# smokoino.net
KiCad netlist of a schematic drawn in EAGLE
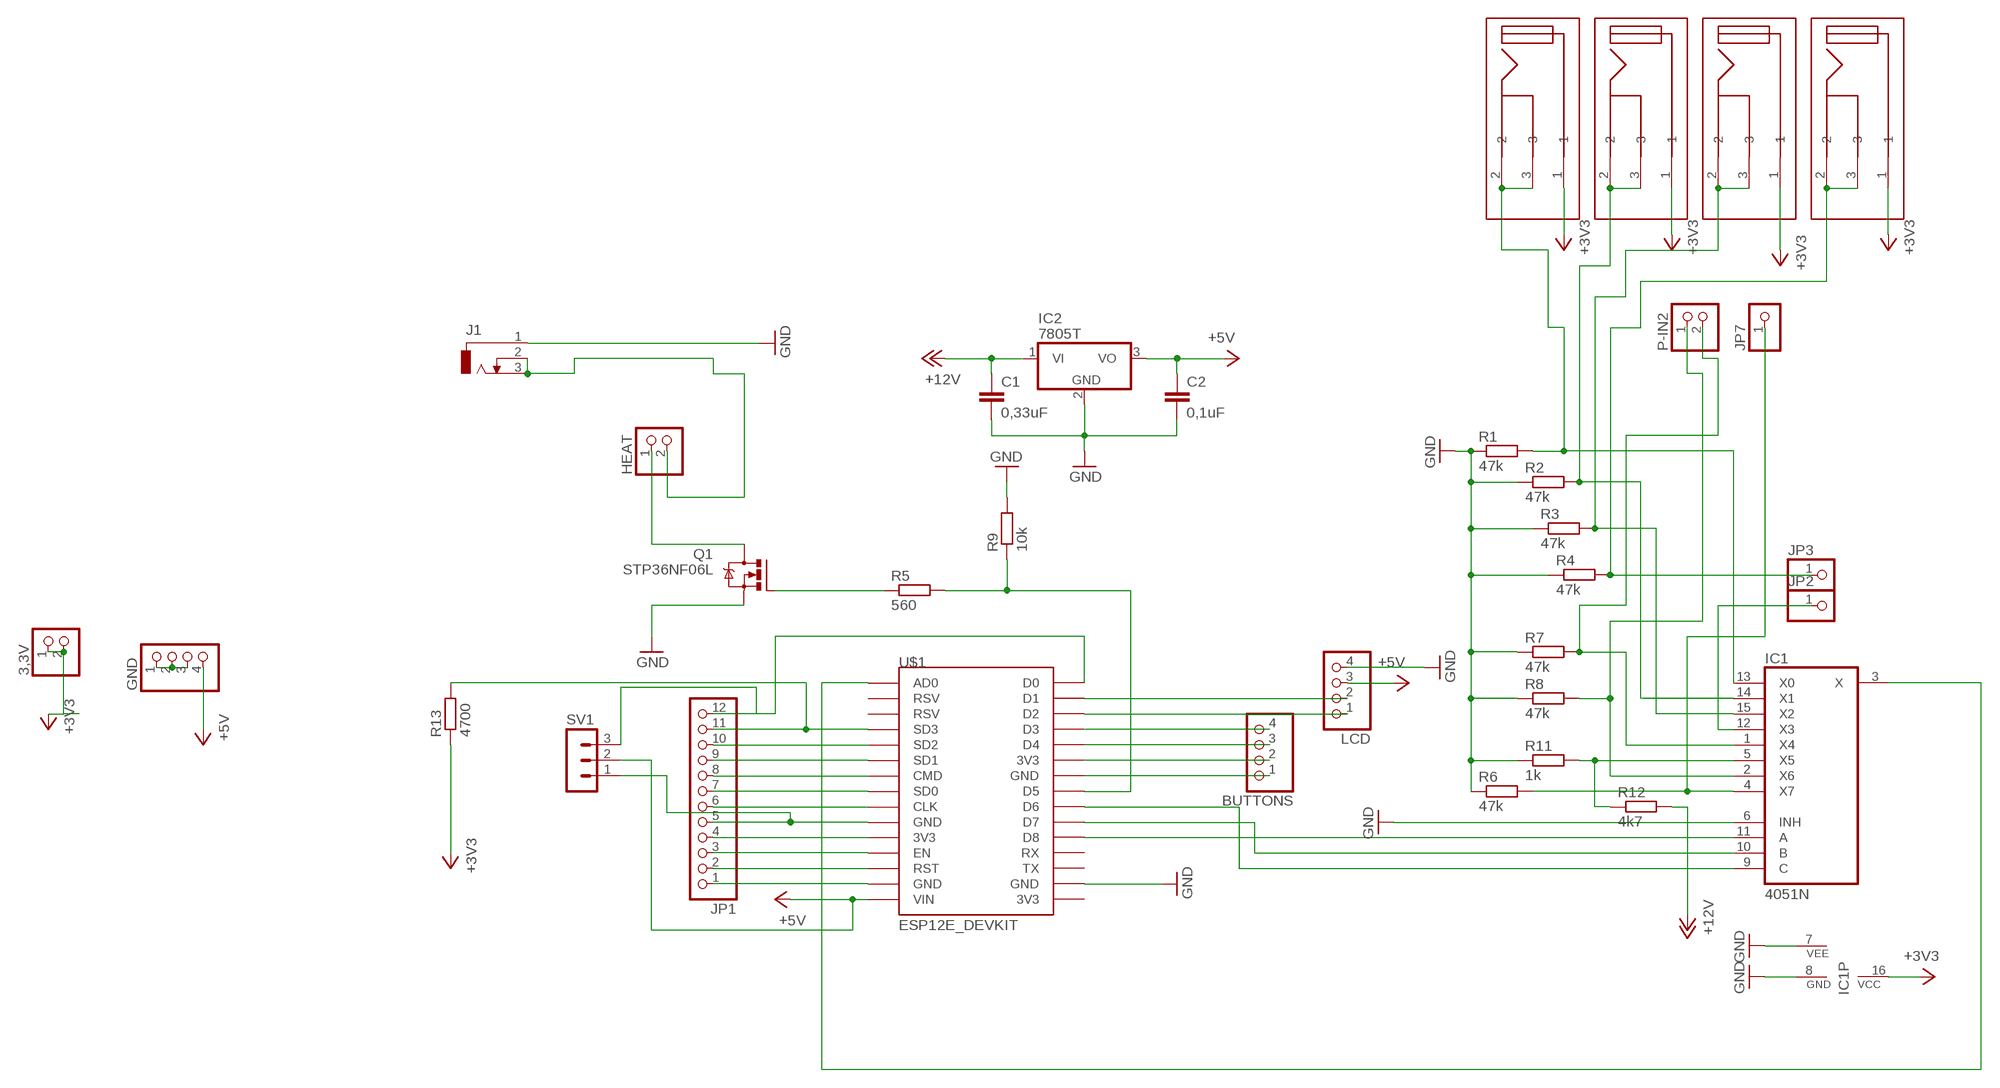
[diagram p0: schematic, sheet 1]

(export (version "E")
  (design (tool "Eeschema 10.0.6"))
  (components
    (comp (ref "3,3V")
      (value "PINHD-1X2")
      (footprint "eagle-import:1X02")
      (libsource (lib "eagle-import") (part "PINHD-1X2"))
    )
    (comp (ref "BUTTONS")
      (value "PINHD-1X4")
      (footprint "eagle-import:1X04")
      (libsource (lib "eagle-import") (part "PINHD-1X4"))
    )
    (comp (ref "C1")
      (value "0,33uF")
      (footprint "eagle-import:C5B2.5")
      (libsource (lib "eagle-import") (part "C5/2.5"))
    )
    (comp (ref "C2")
      (value "0,1uF")
      (footprint "eagle-import:C5B2.5")
      (libsource (lib "eagle-import") (part "C5/2.5"))
    )
    (comp (ref "GND")
      (value "PINHD-1X4")
      (footprint "eagle-import:1X04")
      (libsource (lib "eagle-import") (part "PINHD-1X4"))
    )
    (comp (ref "HEAT")
      (value "PINHD-1X2")
      (footprint "eagle-import:1X02")
      (libsource (lib "eagle-import") (part "PINHD-1X2"))
    )
    (comp (ref "IC1")
      (value "4051N")
      (footprint "eagle-import:DIL16")
      (libsource (lib "eagle-import") (part "4051N"))
    )
    (comp (ref "IC2")
      (value "7805T")
      (footprint "eagle-import:TO220H")
      (libsource (lib "eagle-import") (part "78T05"))
    )
    (comp (ref "J1")
      (value "DCJ0303")
      (footprint "eagle-import:DCJ0303")
      (libsource (lib "eagle-import") (part "DCJ0303"))
    )
    (comp (ref "JP1")
      (value "PINHD-1X12")
      (footprint "eagle-import:1X12")
      (libsource (lib "eagle-import") (part "PINHD-1X12"))
    )
    (comp (ref "JP2")
      (value "PINHD-1X1")
      (footprint "eagle-import:1X01")
      (libsource (lib "eagle-import") (part "PINHD-1X1"))
    )
    (comp (ref "JP3")
      (value "PINHD-1X1")
      (footprint "eagle-import:1X01")
      (libsource (lib "eagle-import") (part "PINHD-1X1"))
    )
    (comp (ref "JP7")
      (value "PINHD-1X1")
      (footprint "eagle-import:1X01")
      (libsource (lib "eagle-import") (part "PINHD-1X1"))
    )
    (comp (ref "LCD")
      (value "PINHD-1X4")
      (footprint "eagle-import:1X04")
      (libsource (lib "eagle-import") (part "PINHD-1X4"))
    )
    (comp (ref "P-IN2")
      (value "PINHD-1X2")
      (footprint "eagle-import:1X02")
      (libsource (lib "eagle-import") (part "PINHD-1X2"))
    )
    (comp (ref "Q1")
      (value "STP36NF06L")
      (footprint "eagle-import:TO220BV")
      (libsource (lib "eagle-import") (part "IRF540"))
    )
    (comp (ref "R1")
      (value "47k")
      (footprint "eagle-import:0207_10")
      (libsource (lib "eagle-import") (part "R-EU_0207/10"))
    )
    (comp (ref "R2")
      (value "47k")
      (footprint "eagle-import:0207_10")
      (libsource (lib "eagle-import") (part "R-EU_0207/10"))
    )
    (comp (ref "R3")
      (value "47k")
      (footprint "eagle-import:0207_10")
      (libsource (lib "eagle-import") (part "R-EU_0207/10"))
    )
    (comp (ref "R4")
      (value "47k")
      (footprint "eagle-import:0207_10")
      (libsource (lib "eagle-import") (part "R-EU_0207/10"))
    )
    (comp (ref "R5")
      (value "560")
      (footprint "eagle-import:0207_10")
      (libsource (lib "eagle-import") (part "R-EU_0207/10"))
    )
    (comp (ref "R6")
      (value "47k")
      (footprint "eagle-import:0207_10")
      (libsource (lib "eagle-import") (part "R-EU_0207/10"))
    )
    (comp (ref "R7")
      (value "47k")
      (footprint "eagle-import:0207_10")
      (libsource (lib "eagle-import") (part "R-EU_0207/10"))
    )
    (comp (ref "R8")
      (value "47k")
      (footprint "eagle-import:0207_10")
      (libsource (lib "eagle-import") (part "R-EU_0207/10"))
    )
    (comp (ref "R9")
      (value "10k")
      (footprint "eagle-import:0207_10")
      (libsource (lib "eagle-import") (part "R-EU_0207/10"))
    )
    (comp (ref "R11")
      (value "1k")
      (footprint "eagle-import:0207_10")
      (libsource (lib "eagle-import") (part "R-EU_0207/10"))
    )
    (comp (ref "R12")
      (value "4k7")
      (footprint "eagle-import:0207_10")
      (libsource (lib "eagle-import") (part "R-EU_0207/10"))
    )
    (comp (ref "R13")
      (value "4700")
      (footprint "eagle-import:0207_10")
      (libsource (lib "eagle-import") (part "R-EU_0207/10"))
    )
    (comp (ref "SV1")
      (value "MA03-1")
      (footprint "eagle-import:MA03-1")
      (libsource (lib "eagle-import") (part "MA03-1"))
    )
    (comp (ref "U$1")
      (value "ESP12E_DEVKIT")
      (footprint "eagle-import:ESP12E_DEVKIT")
      (libsource (lib "eagle-import") (part "ESP12E_DEVKIT"))
    )
    (comp (ref "U$3")
      (value "JACK_2_5")
      (footprint "eagle-import:JACK_2_5")
      (libsource (lib "eagle-import") (part "JACK_2_5"))
    )
    (comp (ref "U$4")
      (value "JACK_2_5")
      (footprint "eagle-import:JACK_2_5")
      (libsource (lib "eagle-import") (part "JACK_2_5"))
    )
    (comp (ref "U$5")
      (value "JACK_2_5")
      (footprint "eagle-import:JACK_2_5")
      (libsource (lib "eagle-import") (part "JACK_2_5"))
    )
    (comp (ref "U$6")
      (value "JACK_2_5")
      (footprint "eagle-import:JACK_2_5")
      (libsource (lib "eagle-import") (part "JACK_2_5"))
    )
  )
  (nets
    (net (code "1") (name "+3V3") (class "Default")
      (node (ref "3,3V") (pin "1") (pinfunction "1_1") (pintype "passive"))
      (node (ref "3,3V") (pin "2") (pinfunction "2_2") (pintype "passive"))
      (node (ref "IC1") (pin "16") (pinfunction "VCC_16") (pintype "power_in"))
      (node (ref "JP1") (pin "4") (pinfunction "4_4") (pintype "passive"))
      (node (ref "R13") (pin "1") (pinfunction "1_1") (pintype "passive"))
      (node (ref "U$1") (pin "3V3@0") (pinfunction "3V3_3V3@0") (pintype "bidirectional"))
      (node (ref "U$3") (pin "1") (pinfunction "1_1") (pintype "bidirectional"))
      (node (ref "U$4") (pin "1") (pinfunction "1_1") (pintype "bidirectional"))
      (node (ref "U$5") (pin "1") (pinfunction "1_1") (pintype "bidirectional"))
      (node (ref "U$6") (pin "1") (pinfunction "1_1") (pintype "bidirectional"))
    )
    (net (code "2") (name "+5V") (class "Default")
      (node (ref "C2") (pin "1") (pinfunction "1_1") (pintype "passive"))
      (node (ref "GND") (pin "4") (pinfunction "4_4") (pintype "passive"))
      (node (ref "IC2") (pin "3") (pinfunction "VO_3") (pintype "passive"))
      (node (ref "LCD") (pin "3") (pinfunction "3_3") (pintype "passive"))
      (node (ref "SV1") (pin "2") (pinfunction "2_2") (pintype "passive"))
      (node (ref "U$1") (pin "VIN") (pinfunction "VIN_VIN") (pintype "bidirectional"))
    )
    (net (code "3") (name "+12V") (class "Default")
      (node (ref "C1") (pin "1") (pinfunction "1_1") (pintype "passive"))
      (node (ref "HEAT") (pin "2") (pinfunction "2_2") (pintype "passive"))
      (node (ref "IC2") (pin "1") (pinfunction "VI_1") (pintype "input"))
      (node (ref "J1") (pin "2") (pinfunction "2_2") (pintype "passive"))
      (node (ref "J1") (pin "3") (pinfunction "3_3") (pintype "passive"))
      (node (ref "R12") (pin "2") (pinfunction "2_2") (pintype "passive"))
    )
    (net (code "4") (name "GND") (class "Default")
      (node (ref "BUTTONS") (pin "1") (pinfunction "1_1") (pintype "passive"))
      (node (ref "C1") (pin "2") (pinfunction "2_2") (pintype "passive"))
      (node (ref "C2") (pin "2") (pinfunction "2_2") (pintype "passive"))
      (node (ref "GND") (pin "1") (pinfunction "1_1") (pintype "passive"))
      (node (ref "GND") (pin "2") (pinfunction "2_2") (pintype "passive"))
      (node (ref "GND") (pin "3") (pinfunction "3_3") (pintype "passive"))
      (node (ref "IC1") (pin "6") (pinfunction "INH_6") (pintype "input"))
      (node (ref "IC1") (pin "7") (pinfunction "VEE_7") (pintype "power_in"))
      (node (ref "IC1") (pin "8") (pinfunction "GND_8") (pintype "power_in"))
      (node (ref "IC2") (pin "2") (pinfunction "GND_2") (pintype "passive"))
      (node (ref "J1") (pin "1") (pinfunction "1_1") (pintype "passive"))
      (node (ref "JP1") (pin "1") (pinfunction "1_1") (pintype "passive"))
      (node (ref "JP1") (pin "5") (pinfunction "5_5") (pintype "passive"))
      (node (ref "LCD") (pin "4") (pinfunction "4_4") (pintype "passive"))
      (node (ref "Q1") (pin "S") (pinfunction "S_S") (pintype "passive"))
      (node (ref "R1") (pin "1") (pinfunction "1_1") (pintype "passive"))
      (node (ref "R11") (pin "1") (pinfunction "1_1") (pintype "passive"))
      (node (ref "R2") (pin "1") (pinfunction "1_1") (pintype "passive"))
      (node (ref "R3") (pin "1") (pinfunction "1_1") (pintype "passive"))
      (node (ref "R4") (pin "1") (pinfunction "1_1") (pintype "passive"))
      (node (ref "R6") (pin "1") (pinfunction "1_1") (pintype "passive"))
      (node (ref "R7") (pin "1") (pinfunction "1_1") (pintype "passive"))
      (node (ref "R8") (pin "1") (pinfunction "1_1") (pintype "passive"))
      (node (ref "R9") (pin "2") (pinfunction "2_2") (pintype "passive"))
      (node (ref "SV1") (pin "1") (pinfunction "1_1") (pintype "passive"))
      (node (ref "U$1") (pin "GND@0") (pinfunction "GND_GND@0") (pintype "bidirectional"))
      (node (ref "U$1") (pin "GND@1") (pinfunction "GND_GND@1") (pintype "bidirectional"))
      (node (ref "U$1") (pin "GND@2") (pinfunction "GND_GND@2") (pintype "bidirectional"))
      (node (ref "U$1") (pin "GND@3") (pinfunction "GND_GND@3") (pintype "bidirectional"))
    )
    (net (code "5") (name "Net-(BUTTONS-Pad2)") (class "Default")
      (node (ref "BUTTONS") (pin "2") (pinfunction "2_2") (pintype "passive"))
      (node (ref "U$1") (pin "3V3@1") (pinfunction "3V3_3V3@1") (pintype "bidirectional"))
    )
    (net (code "6") (name "Net-(BUTTONS-Pad3)") (class "Default")
      (node (ref "BUTTONS") (pin "3") (pinfunction "3_3") (pintype "passive"))
      (node (ref "U$1") (pin "D4") (pinfunction "D4_D4") (pintype "bidirectional"))
    )
    (net (code "7") (name "Net-(BUTTONS-Pad4)") (class "Default")
      (node (ref "BUTTONS") (pin "4") (pinfunction "4_4") (pintype "passive"))
      (node (ref "U$1") (pin "D3") (pinfunction "D3_D3") (pintype "bidirectional"))
    )
    (net (code "8") (name "Net-(HEAT-Pad1)") (class "Default")
      (node (ref "HEAT") (pin "1") (pinfunction "1_1") (pintype "passive"))
      (node (ref "Q1") (pin "D") (pinfunction "D_D") (pintype "passive"))
    )
    (net (code "9") (name "Net-(IC1A-A)") (class "Default")
      (node (ref "IC1") (pin "11") (pinfunction "A_11") (pintype "input"))
      (node (ref "U$1") (pin "D8") (pinfunction "D8_D8") (pintype "bidirectional"))
    )
    (net (code "10") (name "Net-(IC1A-B)") (class "Default")
      (node (ref "IC1") (pin "10") (pinfunction "B_10") (pintype "input"))
      (node (ref "U$1") (pin "D7") (pinfunction "D7_D7") (pintype "bidirectional"))
    )
    (net (code "11") (name "Net-(IC1A-C)") (class "Default")
      (node (ref "IC1") (pin "9") (pinfunction "C_9") (pintype "input"))
      (node (ref "U$1") (pin "D6") (pinfunction "D6_D6") (pintype "bidirectional"))
    )
    (net (code "12") (name "Net-(IC1A-X)") (class "Default")
      (node (ref "IC1") (pin "3") (pinfunction "X_3") (pintype "bidirectional"))
      (node (ref "U$1") (pin "AD0") (pinfunction "AD0_AD0") (pintype "bidirectional"))
    )
    (net (code "13") (name "Net-(IC1A-X0)") (class "Default")
      (node (ref "IC1") (pin "13") (pinfunction "X0_13") (pintype "bidirectional"))
      (node (ref "R1") (pin "2") (pinfunction "2_2") (pintype "passive"))
      (node (ref "U$3") (pin "2") (pinfunction "2_2") (pintype "bidirectional"))
      (node (ref "U$3") (pin "3") (pinfunction "3_3") (pintype "bidirectional"))
    )
    (net (code "14") (name "Net-(IC1A-X1)") (class "Default")
      (node (ref "IC1") (pin "14") (pinfunction "X1_14") (pintype "bidirectional"))
      (node (ref "R2") (pin "2") (pinfunction "2_2") (pintype "passive"))
      (node (ref "U$4") (pin "2") (pinfunction "2_2") (pintype "bidirectional"))
      (node (ref "U$4") (pin "3") (pinfunction "3_3") (pintype "bidirectional"))
    )
    (net (code "15") (name "Net-(IC1A-X2)") (class "Default")
      (node (ref "IC1") (pin "15") (pinfunction "X2_15") (pintype "bidirectional"))
      (node (ref "R3") (pin "2") (pinfunction "2_2") (pintype "passive"))
      (node (ref "U$5") (pin "2") (pinfunction "2_2") (pintype "bidirectional"))
      (node (ref "U$5") (pin "3") (pinfunction "3_3") (pintype "bidirectional"))
    )
    (net (code "16") (name "Net-(IC1A-X3)") (class "Default")
      (node (ref "IC1") (pin "12") (pinfunction "X3_12") (pintype "bidirectional"))
      (node (ref "JP2") (pin "1") (pinfunction "1_1") (pintype "passive"))
    )
    (net (code "17") (name "Net-(IC1A-X4)") (class "Default")
      (node (ref "IC1") (pin "1") (pinfunction "X4_1") (pintype "bidirectional"))
      (node (ref "P-IN2") (pin "2") (pinfunction "2_2") (pintype "passive"))
      (node (ref "R7") (pin "2") (pinfunction "2_2") (pintype "passive"))
    )
    (net (code "18") (name "Net-(IC1A-X5)") (class "Default")
      (node (ref "IC1") (pin "5") (pinfunction "X5_5") (pintype "bidirectional"))
      (node (ref "R11") (pin "2") (pinfunction "2_2") (pintype "passive"))
      (node (ref "R12") (pin "1") (pinfunction "1_1") (pintype "passive"))
    )
    (net (code "19") (name "Net-(IC1A-X6)") (class "Default")
      (node (ref "IC1") (pin "2") (pinfunction "X6_2") (pintype "bidirectional"))
      (node (ref "P-IN2") (pin "1") (pinfunction "1_1") (pintype "passive"))
      (node (ref "R8") (pin "2") (pinfunction "2_2") (pintype "passive"))
    )
    (net (code "20") (name "Net-(IC1A-X7)") (class "Default")
      (node (ref "IC1") (pin "4") (pinfunction "X7_4") (pintype "bidirectional"))
      (node (ref "JP7") (pin "1") (pinfunction "1_1") (pintype "passive"))
      (node (ref "R6") (pin "2") (pinfunction "2_2") (pintype "passive"))
    )
    (net (code "21") (name "Net-(JP1-Pad2)") (class "Default")
      (node (ref "JP1") (pin "2") (pinfunction "2_2") (pintype "passive"))
      (node (ref "U$1") (pin "RST") (pinfunction "RST_RST") (pintype "bidirectional"))
    )
    (net (code "22") (name "Net-(JP1-Pad3)") (class "Default")
      (node (ref "JP1") (pin "3") (pinfunction "3_3") (pintype "passive"))
      (node (ref "U$1") (pin "EN") (pinfunction "EN_EN") (pintype "bidirectional"))
    )
    (net (code "23") (name "Net-(JP1-Pad6)") (class "Default")
      (node (ref "JP1") (pin "6") (pinfunction "6_6") (pintype "passive"))
      (node (ref "U$1") (pin "CLK") (pinfunction "CLK_CLK") (pintype "bidirectional"))
    )
    (net (code "24") (name "Net-(JP1-Pad7)") (class "Default")
      (node (ref "JP1") (pin "7") (pinfunction "7_7") (pintype "passive"))
      (node (ref "U$1") (pin "SD0") (pinfunction "SD0_SD0") (pintype "bidirectional"))
    )
    (net (code "25") (name "Net-(JP1-Pad8)") (class "Default")
      (node (ref "JP1") (pin "8") (pinfunction "8_8") (pintype "passive"))
      (node (ref "U$1") (pin "CMD") (pinfunction "CMD_CMD") (pintype "bidirectional"))
    )
    (net (code "26") (name "Net-(JP1-Pad9)") (class "Default")
      (node (ref "JP1") (pin "9") (pinfunction "9_9") (pintype "passive"))
      (node (ref "U$1") (pin "SD1") (pinfunction "SD1_SD1") (pintype "bidirectional"))
    )
    (net (code "27") (name "Net-(JP1-Pad10)") (class "Default")
      (node (ref "JP1") (pin "10") (pinfunction "10_10") (pintype "passive"))
      (node (ref "U$1") (pin "SD2") (pinfunction "SD2_SD2") (pintype "bidirectional"))
    )
    (net (code "28") (name "Net-(JP1-Pad11)") (class "Default")
      (node (ref "JP1") (pin "11") (pinfunction "11_11") (pintype "passive"))
      (node (ref "R13") (pin "2") (pinfunction "2_2") (pintype "passive"))
      (node (ref "U$1") (pin "SD3") (pinfunction "SD3_SD3") (pintype "bidirectional"))
    )
    (net (code "29") (name "Net-(JP1-Pad12)") (class "Default")
      (node (ref "JP1") (pin "12") (pinfunction "12_12") (pintype "passive"))
      (node (ref "SV1") (pin "3") (pinfunction "3_3") (pintype "passive"))
      (node (ref "U$1") (pin "D0") (pinfunction "D0_D0") (pintype "bidirectional"))
    )
    (net (code "30") (name "Net-(JP3-Pad1)") (class "Default")
      (node (ref "JP3") (pin "1") (pinfunction "1_1") (pintype "passive"))
      (node (ref "R4") (pin "2") (pinfunction "2_2") (pintype "passive"))
      (node (ref "U$6") (pin "2") (pinfunction "2_2") (pintype "bidirectional"))
      (node (ref "U$6") (pin "3") (pinfunction "3_3") (pintype "bidirectional"))
    )
    (net (code "31") (name "Net-(LCD-Pad1)") (class "Default")
      (node (ref "LCD") (pin "1") (pinfunction "1_1") (pintype "passive"))
      (node (ref "U$1") (pin "D2") (pinfunction "D2_D2") (pintype "bidirectional"))
    )
    (net (code "32") (name "Net-(LCD-Pad2)") (class "Default")
      (node (ref "LCD") (pin "2") (pinfunction "2_2") (pintype "passive"))
      (node (ref "U$1") (pin "D1") (pinfunction "D1_D1") (pintype "bidirectional"))
    )
    (net (code "33") (name "Net-(Q1-PadG)") (class "Default")
      (node (ref "Q1") (pin "G") (pinfunction "G_G") (pintype "passive"))
      (node (ref "R5") (pin "1") (pinfunction "1_1") (pintype "passive"))
    )
    (net (code "34") (name "Net-(R5-Pad2)") (class "Default")
      (node (ref "R5") (pin "2") (pinfunction "2_2") (pintype "passive"))
      (node (ref "R9") (pin "1") (pinfunction "1_1") (pintype "passive"))
      (node (ref "U$1") (pin "D5") (pinfunction "D5_D5") (pintype "bidirectional"))
    )
    (net (code "35") (name "unconnected-(U$1-3V3-Pad3V3@2)") (class "Default")
      (node (ref "U$1") (pin "3V3@2") (pinfunction "3V3_3V3@2") (pintype "bidirectional"))
    )
    (net (code "36") (name "unconnected-(U$1-PadRX)") (class "Default")
      (node (ref "U$1") (pin "RX") (pinfunction "RX_RX") (pintype "bidirectional"))
    )
    (net (code "37") (name "unconnected-(U$1-PadTX)") (class "Default")
      (node (ref "U$1") (pin "TX") (pinfunction "TX_TX") (pintype "bidirectional"))
    )
    (net (code "38") (name "unconnected-(U$1-RSV-PadRSV@0)") (class "Default")
      (node (ref "U$1") (pin "RSV@0") (pinfunction "RSV_RSV@0") (pintype "bidirectional"))
    )
    (net (code "39") (name "unconnected-(U$1-RSV-PadRSV@1)") (class "Default")
      (node (ref "U$1") (pin "RSV@1") (pinfunction "RSV_RSV@1") (pintype "bidirectional"))
    )
  )
)
